# connectors.net
KiCad netlist of a schematic drawn in Altium Designer
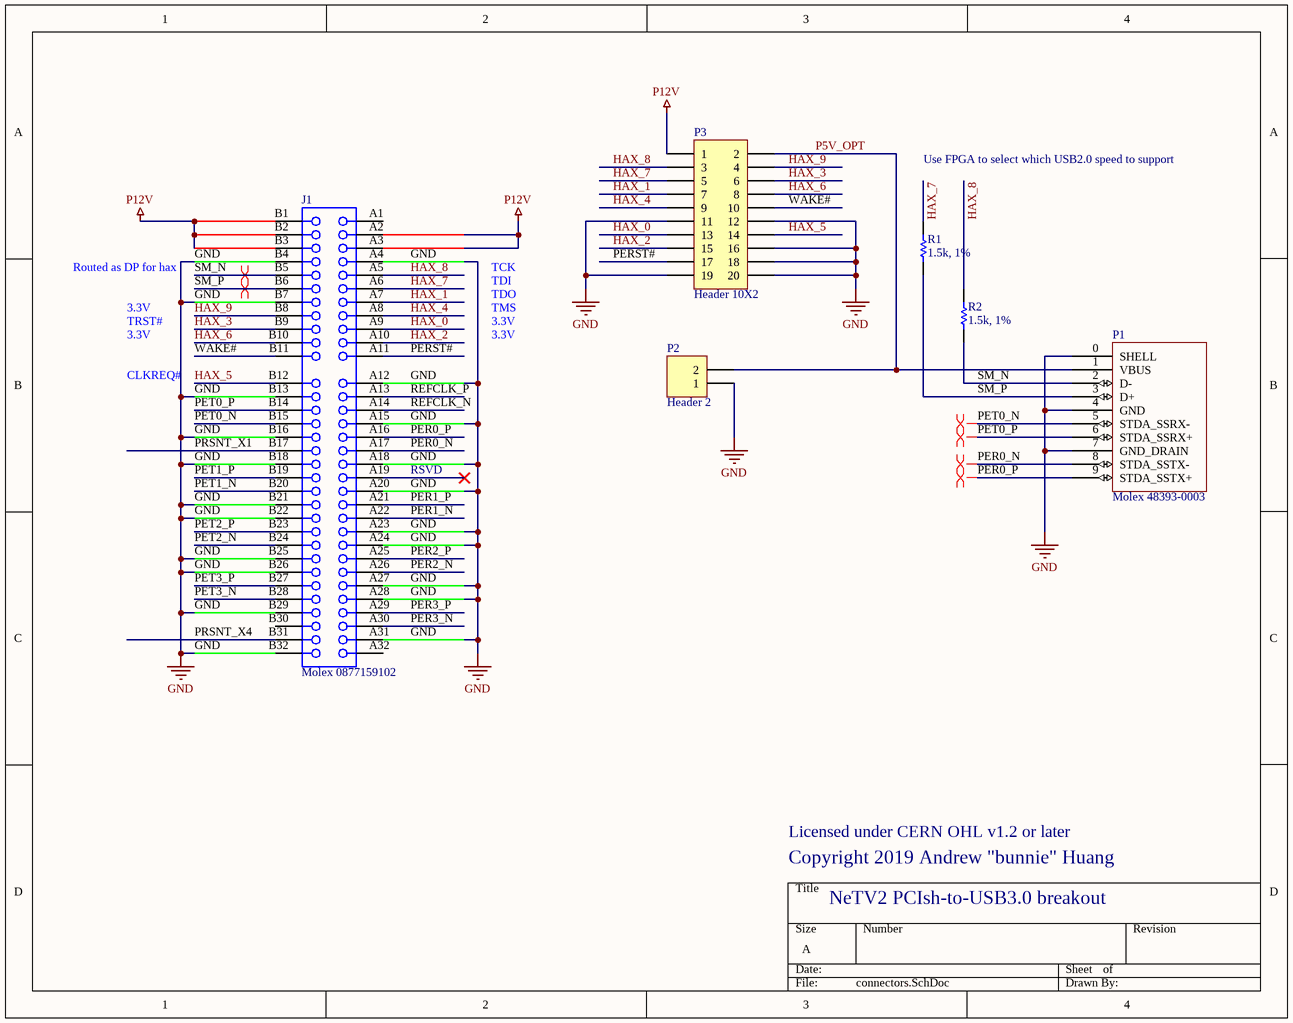
[diagram p0: connectors.SchDoc]

(export (version "E")
  (design (tool "Eeschema 10.0.6"))
  (components
    (comp (ref "J1")
      (value "Molex 0877159102")
      (footprint "BTB1-00-2V64")
      (description "Board-to-Board Connector, PTH, Vertical, Pitch 1.00mm, 64-Position")
      (fields (field (name "MPN") "0877159102"))
      (libsource (lib "CN-2P-F-J64") (part "CN-2P-F-J64"))
    )
    (comp (ref "P1")
      (value "Molex 48393-0003")
      (footprint "MOLEX_48393-0003")
      (description "USB 3.0 Normal A Type R/A")
      (fields (field (name "MPN") "48393-0003"))
      (libsource (lib "commonsch-new") (part "USB_3_TYPE_A"))
    )
    (comp (ref "P2")
      (value "Header 2")
      (footprint "HDR1X2")
      (description "Header, 2-Pin")
      (fields (field (name "PUBLISHER") "Altium Limited"))
      (libsource (lib "Miscellaneous Connectors") (part "Header 2"))
    )
    (comp (ref "P3")
      (value "Header 10X2")
      (footprint "HDR2X10")
      (description "Header, 10-Pin, Dual row")
      (fields (field (name "PUBLISHER") "Altium Limited"))
      (libsource (lib "Miscellaneous Connectors") (part "Header 10X2"))
    )
    (comp (ref "R1")
      (value "1.5k, 1%")
      (footprint "B_RES1206")
      (description "Resistor")
      (fields (field (name "MPN") "ANY"))
      (libsource (lib "Miscellaneous Devices") (part "Res1"))
    )
    (comp (ref "R2")
      (value "1.5k, 1%")
      (footprint "B_RES1206")
      (description "Resistor")
      (fields (field (name "MPN") "ANY"))
      (libsource (lib "Miscellaneous Devices") (part "Res1"))
    )
  )
  (nets
    (net (code "1") (name "/HAX_0") (class "Default")
      (node (ref "J1") (pin "A9") (pinfunction "A9_A9") (pintype "passive"))
      (node (ref "P3") (pin "13") (pinfunction "13_13") (pintype "passive"))
    )
    (net (code "2") (name "/HAX_1") (class "Default")
      (node (ref "J1") (pin "A7") (pinfunction "A7_A7") (pintype "passive"))
      (node (ref "P3") (pin "7") (pinfunction "7_7") (pintype "passive"))
    )
    (net (code "3") (name "/HAX_2") (class "Default")
      (node (ref "J1") (pin "A10") (pinfunction "A10_A10") (pintype "passive"))
      (node (ref "P3") (pin "15") (pinfunction "15_15") (pintype "passive"))
    )
    (net (code "4") (name "/HAX_3") (class "Default")
      (node (ref "J1") (pin "B9") (pinfunction "B9_B9") (pintype "passive"))
      (node (ref "P3") (pin "6") (pinfunction "6_6") (pintype "passive"))
    )
    (net (code "5") (name "/HAX_4") (class "Default")
      (node (ref "J1") (pin "A8") (pinfunction "A8_A8") (pintype "passive"))
      (node (ref "P3") (pin "9") (pinfunction "9_9") (pintype "passive"))
    )
    (net (code "6") (name "/HAX_5") (class "Default")
      (node (ref "J1") (pin "B12") (pinfunction "B12_B12") (pintype "passive"))
      (node (ref "P3") (pin "14") (pinfunction "14_14") (pintype "passive"))
    )
    (net (code "7") (name "/HAX_6") (class "Default")
      (node (ref "J1") (pin "B10") (pinfunction "B10_B10") (pintype "passive"))
      (node (ref "P3") (pin "8") (pinfunction "8_8") (pintype "passive"))
    )
    (net (code "8") (name "/HAX_7") (class "Default")
      (node (ref "J1") (pin "A6") (pinfunction "A6_A6") (pintype "passive"))
      (node (ref "P3") (pin "5") (pinfunction "5_5") (pintype "passive"))
      (node (ref "R1") (pin "1") (pinfunction "1_1") (pintype "passive"))
    )
    (net (code "9") (name "/HAX_8") (class "Default")
      (node (ref "J1") (pin "A5") (pinfunction "A5_A5") (pintype "passive"))
      (node (ref "P3") (pin "3") (pinfunction "3_3") (pintype "passive"))
      (node (ref "R2") (pin "1") (pinfunction "1_1") (pintype "passive"))
    )
    (net (code "10") (name "/HAX_9") (class "Default")
      (node (ref "J1") (pin "B8") (pinfunction "B8_B8") (pintype "passive"))
      (node (ref "P3") (pin "4") (pinfunction "4_4") (pintype "passive"))
    )
    (net (code "11") (name "/P5V_OPT") (class "Default")
      (node (ref "P1") (pin "1") (pinfunction "VBUS_1") (pintype "power_in"))
      (node (ref "P2") (pin "2") (pinfunction "2_2") (pintype "passive"))
      (node (ref "P3") (pin "2") (pinfunction "2_2") (pintype "passive"))
    )
    (net (code "12") (name "/PER0_N") (class "Default")
      (node (ref "J1") (pin "A17") (pinfunction "A17_A17") (pintype "passive"))
      (node (ref "P1") (pin "8") (pinfunction "STDA_SSTX-_8") (pintype "bidirectional"))
    )
    (net (code "13") (name "/PER0_P") (class "Default")
      (node (ref "J1") (pin "A16") (pinfunction "A16_A16") (pintype "passive"))
      (node (ref "P1") (pin "9") (pinfunction "STDA_SSTX+_9") (pintype "bidirectional"))
    )
    (net (code "14") (name "/PER1_N") (class "Default")
      (node (ref "J1") (pin "A22") (pinfunction "A22_A22") (pintype "passive"))
    )
    (net (code "15") (name "/PER1_P") (class "Default")
      (node (ref "J1") (pin "A21") (pinfunction "A21_A21") (pintype "passive"))
    )
    (net (code "16") (name "/PER2_N") (class "Default")
      (node (ref "J1") (pin "A26") (pinfunction "A26_A26") (pintype "passive"))
    )
    (net (code "17") (name "/PER2_P") (class "Default")
      (node (ref "J1") (pin "A25") (pinfunction "A25_A25") (pintype "passive"))
    )
    (net (code "18") (name "/PER3_N") (class "Default")
      (node (ref "J1") (pin "A30") (pinfunction "A30_A30") (pintype "passive"))
    )
    (net (code "19") (name "/PER3_P") (class "Default")
      (node (ref "J1") (pin "A29") (pinfunction "A29_A29") (pintype "passive"))
    )
    (net (code "20") (name "/PERST#") (class "Default")
      (node (ref "J1") (pin "A11") (pinfunction "A11_A11") (pintype "passive"))
      (node (ref "P3") (pin "17") (pinfunction "17_17") (pintype "passive"))
    )
    (net (code "21") (name "/PET0_N") (class "Default")
      (node (ref "J1") (pin "B15") (pinfunction "B15_B15") (pintype "passive"))
      (node (ref "P1") (pin "5") (pinfunction "STDA_SSRX-_5") (pintype "bidirectional"))
    )
    (net (code "22") (name "/PET0_P") (class "Default")
      (node (ref "J1") (pin "B14") (pinfunction "B14_B14") (pintype "passive"))
      (node (ref "P1") (pin "6") (pinfunction "STDA_SSRX+_6") (pintype "bidirectional"))
    )
    (net (code "23") (name "/PET1_N") (class "Default")
      (node (ref "J1") (pin "B20") (pinfunction "B20_B20") (pintype "passive"))
    )
    (net (code "24") (name "/PET1_P") (class "Default")
      (node (ref "J1") (pin "B19") (pinfunction "B19_B19") (pintype "passive"))
    )
    (net (code "25") (name "/PET2_N") (class "Default")
      (node (ref "J1") (pin "B24") (pinfunction "B24_B24") (pintype "passive"))
    )
    (net (code "26") (name "/PET2_P") (class "Default")
      (node (ref "J1") (pin "B23") (pinfunction "B23_B23") (pintype "passive"))
    )
    (net (code "27") (name "/PET3_N") (class "Default")
      (node (ref "J1") (pin "B28") (pinfunction "B28_B28") (pintype "passive"))
    )
    (net (code "28") (name "/PET3_P") (class "Default")
      (node (ref "J1") (pin "B27") (pinfunction "B27_B27") (pintype "passive"))
    )
    (net (code "29") (name "/PRSNT_X1") (class "Default")
      (node (ref "J1") (pin "B17") (pinfunction "B17_B17") (pintype "passive"))
    )
    (net (code "30") (name "/PRSNT_X4") (class "Default")
      (node (ref "J1") (pin "B31") (pinfunction "B31_B31") (pintype "passive"))
    )
    (net (code "31") (name "/REFCLK_N") (class "Default")
      (node (ref "J1") (pin "A14") (pinfunction "A14_A14") (pintype "passive"))
    )
    (net (code "32") (name "/REFCLK_P") (class "Default")
      (node (ref "J1") (pin "A13") (pinfunction "A13_A13") (pintype "passive"))
    )
    (net (code "33") (name "/SM_N") (class "Default")
      (node (ref "J1") (pin "B5") (pinfunction "B5_B5") (pintype "passive"))
      (node (ref "P1") (pin "2") (pinfunction "D-_2") (pintype "bidirectional"))
      (node (ref "R2") (pin "2") (pinfunction "2_2") (pintype "passive"))
    )
    (net (code "34") (name "/SM_P") (class "Default")
      (node (ref "J1") (pin "B6") (pinfunction "B6_B6") (pintype "passive"))
      (node (ref "P1") (pin "3") (pinfunction "D+_3") (pintype "bidirectional"))
      (node (ref "R1") (pin "2") (pinfunction "2_2") (pintype "passive"))
    )
    (net (code "35") (name "/WAKE#") (class "Default")
      (node (ref "J1") (pin "B11") (pinfunction "B11_B11") (pintype "passive"))
      (node (ref "P3") (pin "10") (pinfunction "10_10") (pintype "passive"))
    )
    (net (code "36") (name "GND") (class "Default")
      (node (ref "J1") (pin "A12") (pinfunction "A12_A12") (pintype "passive"))
      (node (ref "J1") (pin "A15") (pinfunction "A15_A15") (pintype "passive"))
      (node (ref "J1") (pin "A18") (pinfunction "A18_A18") (pintype "passive"))
      (node (ref "J1") (pin "A20") (pinfunction "A20_A20") (pintype "passive"))
      (node (ref "J1") (pin "A23") (pinfunction "A23_A23") (pintype "passive"))
      (node (ref "J1") (pin "A24") (pinfunction "A24_A24") (pintype "passive"))
      (node (ref "J1") (pin "A27") (pinfunction "A27_A27") (pintype "passive"))
      (node (ref "J1") (pin "A28") (pinfunction "A28_A28") (pintype "passive"))
      (node (ref "J1") (pin "A31") (pinfunction "A31_A31") (pintype "passive"))
      (node (ref "J1") (pin "A4") (pinfunction "A4_A4") (pintype "passive"))
      (node (ref "J1") (pin "B13") (pinfunction "B13_B13") (pintype "passive"))
      (node (ref "J1") (pin "B16") (pinfunction "B16_B16") (pintype "passive"))
      (node (ref "J1") (pin "B18") (pinfunction "B18_B18") (pintype "passive"))
      (node (ref "J1") (pin "B21") (pinfunction "B21_B21") (pintype "passive"))
      (node (ref "J1") (pin "B22") (pinfunction "B22_B22") (pintype "passive"))
      (node (ref "J1") (pin "B25") (pinfunction "B25_B25") (pintype "passive"))
      (node (ref "J1") (pin "B26") (pinfunction "B26_B26") (pintype "passive"))
      (node (ref "J1") (pin "B29") (pinfunction "B29_B29") (pintype "passive"))
      (node (ref "J1") (pin "B32") (pinfunction "B32_B32") (pintype "passive"))
      (node (ref "J1") (pin "B4") (pinfunction "B4_B4") (pintype "passive"))
      (node (ref "J1") (pin "B7") (pinfunction "B7_B7") (pintype "passive"))
      (node (ref "P1") (pin "0") (pinfunction "SHELL_0") (pintype "passive"))
      (node (ref "P1") (pin "4") (pinfunction "GND_4") (pintype "power_in"))
      (node (ref "P1") (pin "7") (pinfunction "GND_DRAIN_7") (pintype "power_in"))
      (node (ref "P2") (pin "1") (pinfunction "1_1") (pintype "passive"))
      (node (ref "P3") (pin "11") (pinfunction "11_11") (pintype "passive"))
      (node (ref "P3") (pin "12") (pinfunction "12_12") (pintype "passive"))
      (node (ref "P3") (pin "16") (pinfunction "16_16") (pintype "passive"))
      (node (ref "P3") (pin "18") (pinfunction "18_18") (pintype "passive"))
      (node (ref "P3") (pin "19") (pinfunction "19_19") (pintype "passive"))
      (node (ref "P3") (pin "20") (pinfunction "20_20") (pintype "passive"))
    )
    (net (code "37") (name "P12V") (class "Default")
      (node (ref "J1") (pin "A2") (pinfunction "A2_A2") (pintype "passive"))
      (node (ref "J1") (pin "A3") (pinfunction "A3_A3") (pintype "passive"))
      (node (ref "J1") (pin "B1") (pinfunction "B1_B1") (pintype "passive"))
      (node (ref "J1") (pin "B2") (pinfunction "B2_B2") (pintype "passive"))
      (node (ref "J1") (pin "B3") (pinfunction "B3_B3") (pintype "passive"))
      (node (ref "P3") (pin "1") (pinfunction "1_1") (pintype "passive"))
    )
    (net (code "38") (name "unconnected-(J1-PadA1)") (class "Default")
      (node (ref "J1") (pin "A1") (pinfunction "A1_A1") (pintype "passive"))
    )
    (net (code "39") (name "unconnected-(J1-PadA19)") (class "Default")
      (node (ref "J1") (pin "A19") (pinfunction "A19_A19") (pintype "passive+no_connect"))
    )
    (net (code "40") (name "unconnected-(J1-PadA32)") (class "Default")
      (node (ref "J1") (pin "A32") (pinfunction "A32_A32") (pintype "passive"))
    )
    (net (code "41") (name "unconnected-(J1-PadB30)") (class "Default")
      (node (ref "J1") (pin "B30") (pinfunction "B30_B30") (pintype "passive"))
    )
  )
)
